# HDMI.net
KiCad netlist of a schematic drawn in Altium Designer
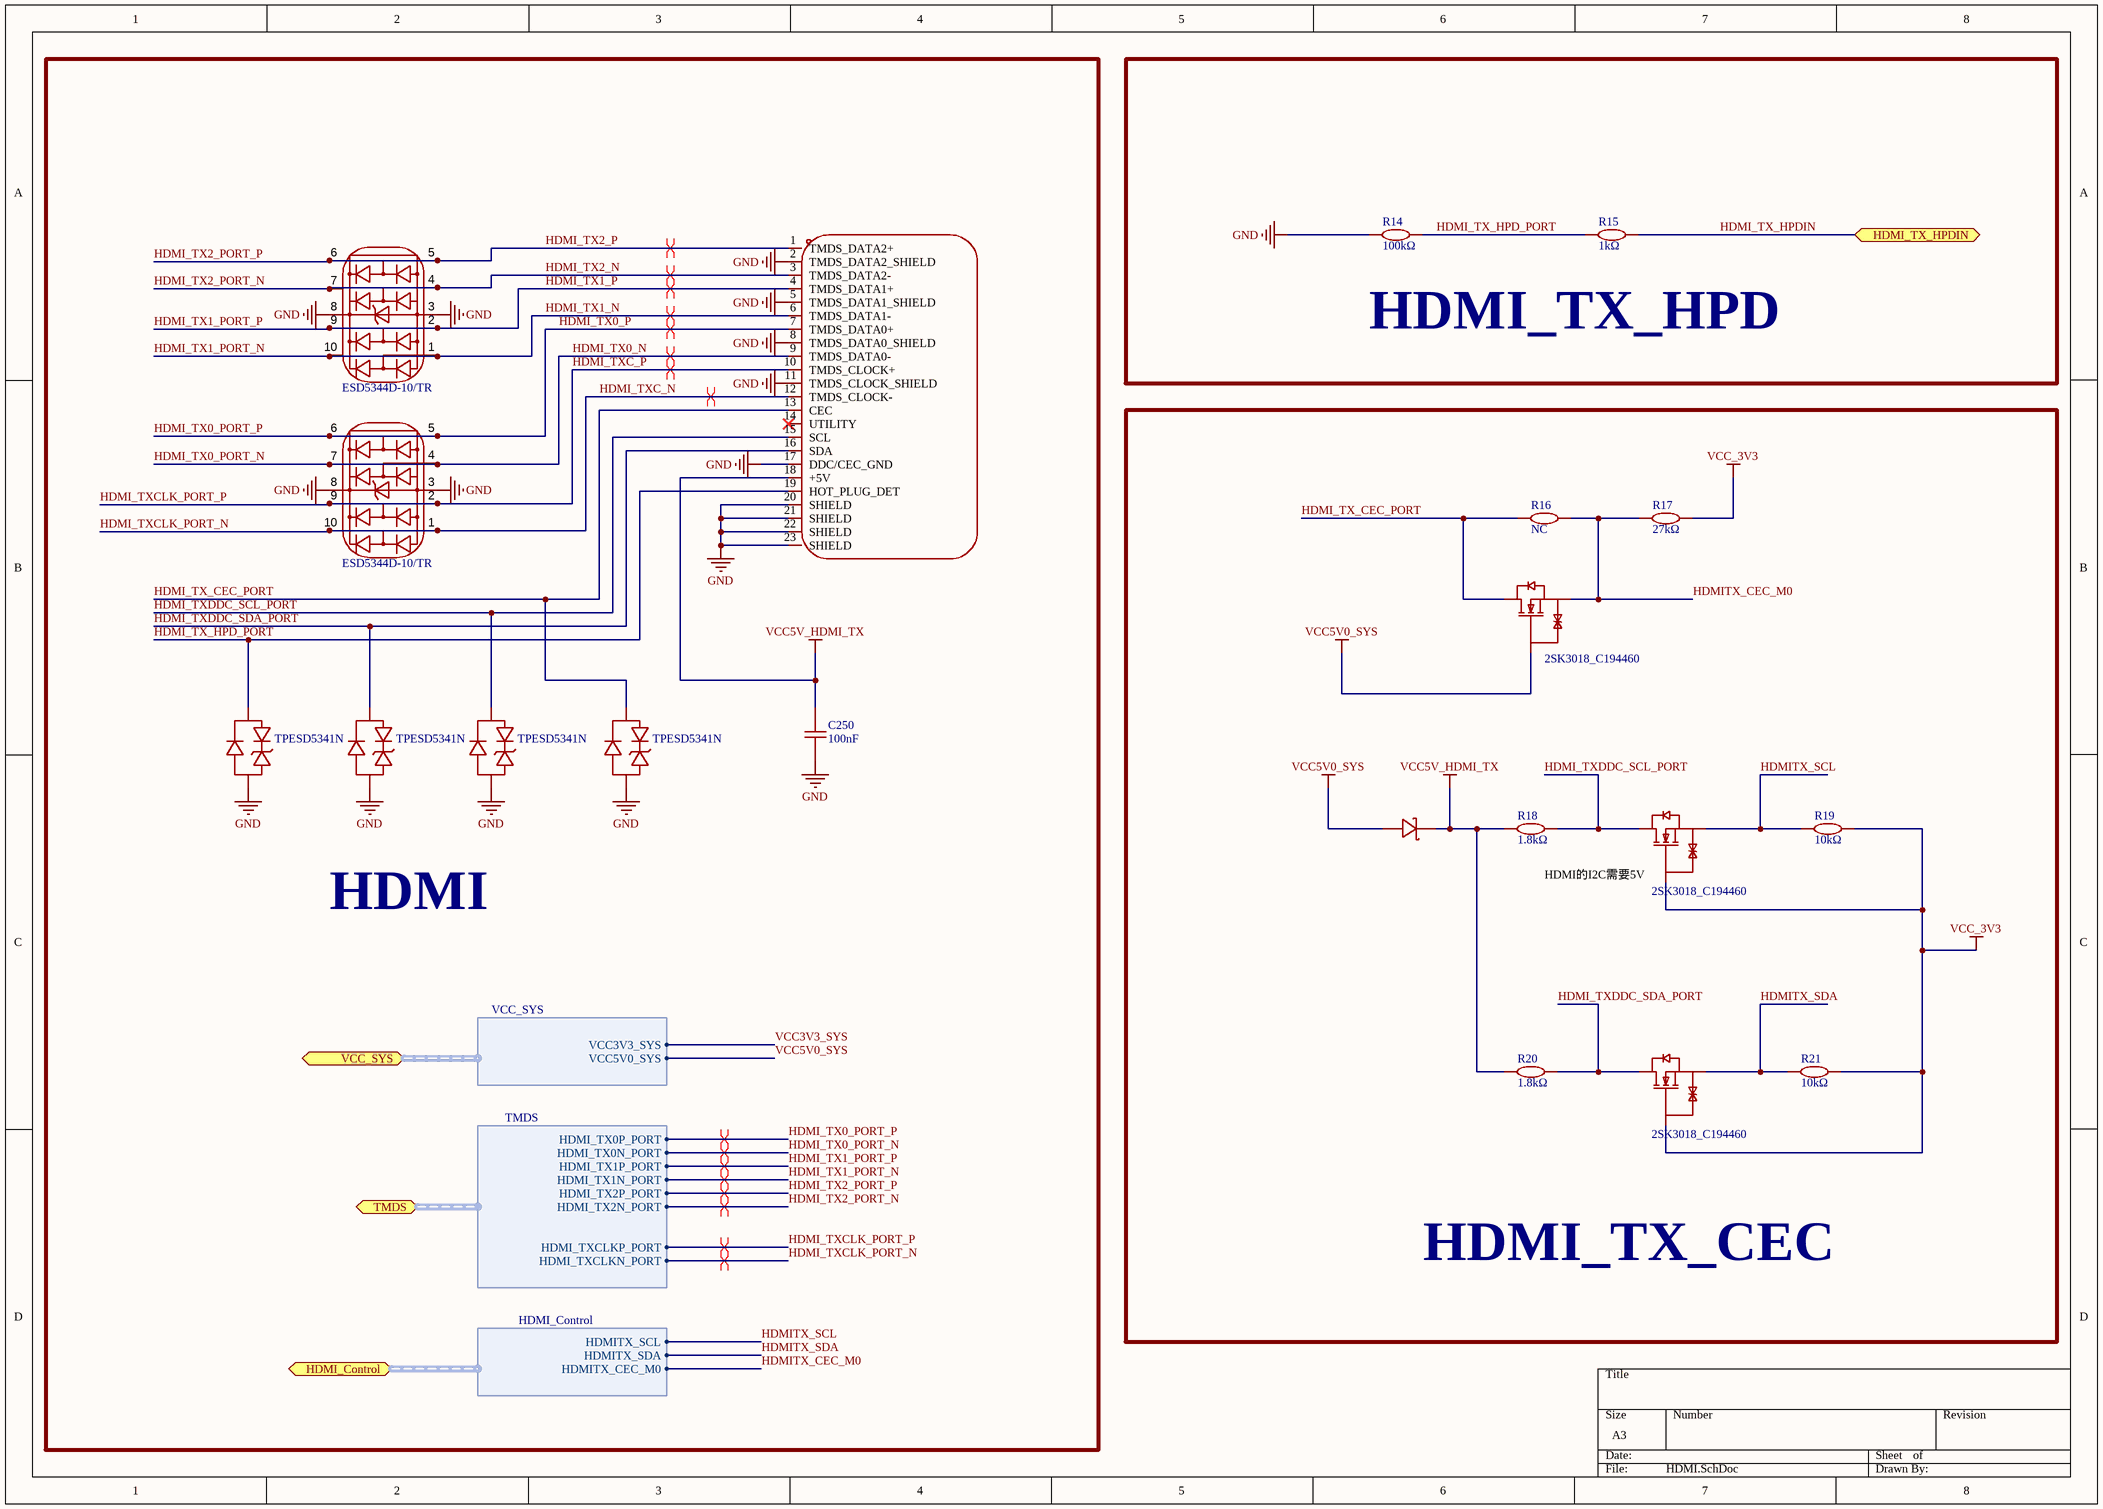
[diagram p0: HDMI.SchDoc]

(export (version "E")
  (design (tool "Eeschema 10.0.6"))
  (components
    (comp (ref "C250")
      (value "100nF")
      (footprint "C0402")
      (description "50V 100nF X7R ±10% 0402 Ceramic Capacitors ROHS")
      (libsource (lib "RLC") (part "100nF"))
    )
    (comp (ref "CN1")
      (value "KH-HDMI-19P-Cu")
      (footprint "HDMI-SMD_KH-HDMI-19P-CU")
      (description "HDMI-A SMD USB, DVI, HDMI Connector Assemblies ROHS")
      (fields (field (name "MANUFACTURER") "kinghelm(金航标)"))
      (libsource (lib "Connector") (part "KH-HDMI-19P-Cu"))
    )
    (comp (ref "D1")
      (value "ESD5344D-10/TR")
      (footprint "DFN2510-10_L2.5-W1.0-P0.50-BL")
      (libsource (lib "IC") (part "ESD5344D-10/TR"))
    )
    (comp (ref "D2")
      (value "ESD5344D-10/TR")
      (footprint "DFN2510-10_L2.5-W1.0-P0.50-BL")
      (libsource (lib "IC") (part "ESD5344D-10/TR"))
    )
    (comp (ref "D3")
      (value "TPESD5341N")
      (footprint "X1-DFN1006-2_L1.0-W0.6-RD")
      (description "VRWM:5V, IPP:3.3A, CJ:0.35pF")
      (libsource (lib "IC") (part "TPESD5341N"))
    )
    (comp (ref "D4")
      (value "TPESD5341N")
      (footprint "X1-DFN1006-2_L1.0-W0.6-RD")
      (description "VRWM:5V, IPP:3.3A, CJ:0.35pF")
      (libsource (lib "IC") (part "TPESD5341N"))
    )
    (comp (ref "D5")
      (value "TPESD5341N")
      (footprint "X1-DFN1006-2_L1.0-W0.6-RD")
      (description "VRWM:5V, IPP:3.3A, CJ:0.35pF")
      (libsource (lib "IC") (part "TPESD5341N"))
    )
    (comp (ref "D6")
      (value "TPESD5341N")
      (footprint "X1-DFN1006-2_L1.0-W0.6-RD")
      (description "VRWM:5V, IPP:3.3A, CJ:0.35pF")
      (libsource (lib "IC") (part "TPESD5341N"))
    )
    (comp (ref "D7")
      (value "1N5819WS")
      (footprint "SOD-323_L1.8-W1.3-LS2.5-RD")
      (description "25A 40V 600mV@1A 1A SOD-323 Single Diodes ROHS")
      (fields (field (name "MANUFACTURER") "Hottech(合科泰)"))
      (libsource (lib "LED") (part "1N5819WS_C191023"))
    )
    (comp (ref "Q1")
      (value "2SK3018_C194460")
      (footprint "SOT-23-3_L2.9-W1.3-P1.90-LS2.3-BR")
      (description "N沟道,30V,100mA")
      (libsource (lib "Transistor") (part "2SK3018_C194460"))
    )
    (comp (ref "Q2")
      (value "2SK3018_C194460")
      (footprint "SOT-23-3_L2.9-W1.3-P1.90-LS2.3-BR")
      (description "N沟道,30V,100mA")
      (libsource (lib "Transistor") (part "2SK3018_C194460"))
    )
    (comp (ref "Q3")
      (value "2SK3018_C194460")
      (footprint "SOT-23-3_L2.9-W1.3-P1.90-LS2.3-BR")
      (description "N沟道,30V,100mA")
      (libsource (lib "Transistor") (part "2SK3018_C194460"))
    )
    (comp (ref "R14")
      (value "100kΩ")
      (footprint "R0402")
      (description "100kΩ 62.5mW 50V ±100ppm/℃ Thick Film Resistor ±1% 0402 Chip Resistor - Surface Mount ROHS")
      (libsource (lib "RLC") (part "100kΩ"))
    )
    (comp (ref "R15")
      (value "1kΩ")
      (footprint "R0402")
      (description "1kΩ 62.5mW 50V ±100ppm/℃ Thick Film Resistor ±1% 0402 Chip Resistor - Surface Mount ROHS")
      (libsource (lib "RLC") (part "1kΩ"))
    )
    (comp (ref "R16")
      (value "NC")
      (footprint "R0402")
      (description "0Ω 62.5mW 50V Thick Film Resistor ±1% 0402 Chip Resistor - Surface Mount ROHS")
      (libsource (lib "RLC") (part "0Ω"))
    )
    (comp (ref "R17")
      (value "27kΩ")
      (footprint "R0402")
      (description "小尺寸、重量轻。降低组装成本,与贴片机匹配。适用于波峰焊和回流焊")
      (libsource (lib "RLC") (part "27kΩ"))
    )
    (comp (ref "R18")
      (value "1.8kΩ")
      (footprint "R0402")
      (description "62.5mW 1.8kΩ 50V ±100ppm/℃ Thick Film Resistor ±1% 0402 Chip Resistor - Surface Mount ROHS")
      (libsource (lib "RLC") (part "1.8kΩ"))
    )
    (comp (ref "R19")
      (value "10kΩ")
      (footprint "R0402")
      (description "62.5mW 10kΩ 50V ±100ppm/℃ Thick Film Resistor ±1% 0402 Chip Resistor - Surface Mount ROHS")
      (libsource (lib "RLC") (part "10kΩ"))
    )
    (comp (ref "R20")
      (value "1.8kΩ")
      (footprint "R0402")
      (description "62.5mW 1.8kΩ 50V ±100ppm/℃ Thick Film Resistor ±1% 0402 Chip Resistor - Surface Mount ROHS")
      (libsource (lib "RLC") (part "1.8kΩ"))
    )
    (comp (ref "R21")
      (value "10kΩ")
      (footprint "R0402")
      (description "62.5mW 10kΩ 50V ±100ppm/℃ Thick Film Resistor ±1% 0402 Chip Resistor - Surface Mount ROHS")
      (libsource (lib "RLC") (part "10kΩ"))
    )
  )
  (nets
    (net (code "4") (name "/HDMITX_CEC_M0") (class "Default")
      (node (ref "Q1") (pin "2") (pinfunction "S_2") (pintype "passive"))
      (node (ref "R16") (pin "2") (pinfunction "2_2") (pintype "passive"))
      (node (ref "R17") (pin "1") (pinfunction "1_1") (pintype "passive"))
    )
    (net (code "5") (name "/HDMITX_SCL") (class "Default")
      (node (ref "Q2") (pin "2") (pinfunction "S_2") (pintype "passive"))
      (node (ref "R19") (pin "1") (pinfunction "1_1") (pintype "passive"))
    )
    (net (code "6") (name "/HDMITX_SDA") (class "Default")
      (node (ref "Q3") (pin "2") (pinfunction "S_2") (pintype "passive"))
      (node (ref "R21") (pin "1") (pinfunction "1_1") (pintype "passive"))
    )
    (net (code "7") (name "/HDMI_TX0_N") (class "Default")
      (node (ref "CN1") (pin "9") (pinfunction "TMDS_DATA0-_9") (pintype "passive"))
      (node (ref "D2") (pin "4") (pinfunction "4_4") (pintype "passive"))
      (node (ref "D2") (pin "7") (pinfunction "7_7") (pintype "passive"))
    )
    (net (code "8") (name "/HDMI_TX0_P") (class "Default")
      (node (ref "CN1") (pin "7") (pinfunction "TMDS_DATA0+_7") (pintype "passive"))
      (node (ref "D2") (pin "5") (pinfunction "5_5") (pintype "passive"))
      (node (ref "D2") (pin "6") (pinfunction "6_6") (pintype "passive"))
    )
    (net (code "9") (name "/HDMI_TX1_N") (class "Default")
      (node (ref "CN1") (pin "6") (pinfunction "TMDS_DATA1-_6") (pintype "passive"))
      (node (ref "D1") (pin "1") (pinfunction "1_1") (pintype "passive"))
      (node (ref "D1") (pin "10") (pinfunction "10_10") (pintype "passive"))
    )
    (net (code "10") (name "/HDMI_TX1_P") (class "Default")
      (node (ref "CN1") (pin "4") (pinfunction "TMDS_DATA1+_4") (pintype "passive"))
      (node (ref "D1") (pin "2") (pinfunction "2_2") (pintype "passive"))
      (node (ref "D1") (pin "9") (pinfunction "9_9") (pintype "passive"))
    )
    (net (code "11") (name "/HDMI_TX2_N") (class "Default")
      (node (ref "CN1") (pin "3") (pinfunction "TMDS_DATA2-_3") (pintype "passive"))
      (node (ref "D1") (pin "4") (pinfunction "4_4") (pintype "passive"))
      (node (ref "D1") (pin "7") (pinfunction "7_7") (pintype "passive"))
    )
    (net (code "12") (name "/HDMI_TX2_P") (class "Default")
      (node (ref "CN1") (pin "1") (pinfunction "TMDS_DATA2+_1") (pintype "passive"))
      (node (ref "D1") (pin "5") (pinfunction "5_5") (pintype "passive"))
      (node (ref "D1") (pin "6") (pinfunction "6_6") (pintype "passive"))
    )
    (net (code "13") (name "/HDMI_TXCLK_PORT_N") (class "Default")
      (node (ref "CN1") (pin "12") (pinfunction "TMDS_CLOCK-_12") (pintype "passive"))
      (node (ref "D2") (pin "1") (pinfunction "1_1") (pintype "passive"))
      (node (ref "D2") (pin "10") (pinfunction "10_10") (pintype "passive"))
    )
    (net (code "14") (name "/HDMI_TXCLK_PORT_P") (class "Default")
      (node (ref "CN1") (pin "10") (pinfunction "TMDS_CLOCK+_10") (pintype "passive"))
      (node (ref "D2") (pin "2") (pinfunction "2_2") (pintype "passive"))
      (node (ref "D2") (pin "9") (pinfunction "9_9") (pintype "passive"))
    )
    (net (code "15") (name "/HDMI_TXDDC_SCL_PORT") (class "Default")
      (node (ref "CN1") (pin "15") (pinfunction "SCL_15") (pintype "passive"))
      (node (ref "D5") (pin "1") (pinfunction "1_1") (pintype "passive"))
      (node (ref "Q2") (pin "3") (pinfunction "D_3") (pintype "passive"))
      (node (ref "R18") (pin "2") (pinfunction "2_2") (pintype "passive"))
    )
    (net (code "16") (name "/HDMI_TXDDC_SDA_PORT") (class "Default")
      (node (ref "CN1") (pin "16") (pinfunction "SDA_16") (pintype "passive"))
      (node (ref "D4") (pin "1") (pinfunction "1_1") (pintype "passive"))
      (node (ref "Q3") (pin "3") (pinfunction "D_3") (pintype "passive"))
      (node (ref "R20") (pin "2") (pinfunction "2_2") (pintype "passive"))
    )
    (net (code "17") (name "/HDMI_TX_CEC_PORT") (class "Default")
      (node (ref "CN1") (pin "13") (pinfunction "CEC_13") (pintype "passive"))
      (node (ref "D6") (pin "1") (pinfunction "1_1") (pintype "passive"))
      (node (ref "Q1") (pin "3") (pinfunction "D_3") (pintype "passive"))
      (node (ref "R16") (pin "1") (pinfunction "1_1") (pintype "passive"))
    )
    (net (code "18") (name "/HDMI_TX_HPDIN") (class "Default")
      (node (ref "R15") (pin "2") (pinfunction "2_2") (pintype "passive"))
    )
    (net (code "19") (name "/HDMI_TX_HPD_PORT") (class "Default")
      (node (ref "CN1") (pin "19") (pinfunction "HOT_PLUG_DET_19") (pintype "passive"))
      (node (ref "D3") (pin "1") (pinfunction "1_1") (pintype "passive"))
      (node (ref "R14") (pin "2") (pinfunction "2_2") (pintype "passive"))
      (node (ref "R15") (pin "1") (pinfunction "1_1") (pintype "passive"))
    )
    (net (code "24") (name "GND") (class "Default")
      (node (ref "C250") (pin "1") (pinfunction "1_1") (pintype "passive"))
      (node (ref "CN1") (pin "11") (pinfunction "TMDS_CLOCK_SHIELD_11") (pintype "passive"))
      (node (ref "CN1") (pin "17") (pinfunction "DDC/CEC_GND_17") (pintype "passive"))
      (node (ref "CN1") (pin "2") (pinfunction "TMDS_DATA2_SHIELD_2") (pintype "passive"))
      (node (ref "CN1") (pin "20") (pinfunction "SHIELD_20") (pintype "passive"))
      (node (ref "CN1") (pin "21") (pinfunction "SHIELD_21") (pintype "passive"))
      (node (ref "CN1") (pin "22") (pinfunction "SHIELD_22") (pintype "passive"))
      (node (ref "CN1") (pin "23") (pinfunction "SHIELD_23") (pintype "passive"))
      (node (ref "CN1") (pin "5") (pinfunction "TMDS_DATA1_SHIELD_5") (pintype "passive"))
      (node (ref "CN1") (pin "8") (pinfunction "TMDS_DATA0_SHIELD_8") (pintype "passive"))
      (node (ref "D1") (pin "3") (pinfunction "3_3") (pintype "passive"))
      (node (ref "D1") (pin "8") (pinfunction "8_8") (pintype "passive"))
      (node (ref "D2") (pin "3") (pinfunction "3_3") (pintype "passive"))
      (node (ref "D2") (pin "8") (pinfunction "8_8") (pintype "passive"))
      (node (ref "D3") (pin "2") (pinfunction "2_2") (pintype "passive"))
      (node (ref "D4") (pin "2") (pinfunction "2_2") (pintype "passive"))
      (node (ref "D5") (pin "2") (pinfunction "2_2") (pintype "passive"))
      (node (ref "D6") (pin "2") (pinfunction "2_2") (pintype "passive"))
      (node (ref "R14") (pin "1") (pinfunction "1_1") (pintype "passive"))
    )
    (net (code "25") (name "VCC5V0_SYS") (class "Default")
      (node (ref "D7") (pin "2") (pinfunction "A_2") (pintype "passive"))
      (node (ref "Q1") (pin "1") (pinfunction "G_1") (pintype "passive"))
    )
    (net (code "26") (name "VCC5V_HDMI_TX") (class "Default")
      (node (ref "C250") (pin "2") (pinfunction "2_2") (pintype "passive"))
      (node (ref "CN1") (pin "18") (pinfunction "+5V_18") (pintype "passive"))
      (node (ref "D7") (pin "1") (pinfunction "K_1") (pintype "passive"))
      (node (ref "R18") (pin "1") (pinfunction "1_1") (pintype "passive"))
      (node (ref "R20") (pin "1") (pinfunction "1_1") (pintype "passive"))
    )
    (net (code "27") (name "VCC_3V3") (class "Default")
      (node (ref "Q2") (pin "1") (pinfunction "G_1") (pintype "passive"))
      (node (ref "Q3") (pin "1") (pinfunction "G_1") (pintype "passive"))
      (node (ref "R17") (pin "2") (pinfunction "2_2") (pintype "passive"))
      (node (ref "R19") (pin "2") (pinfunction "2_2") (pintype "passive"))
      (node (ref "R21") (pin "2") (pinfunction "2_2") (pintype "passive"))
    )
    (net (code "28") (name "unconnected-(CN1-UTILITY-Pad14)") (class "Default")
      (node (ref "CN1") (pin "14") (pinfunction "UTILITY_14") (pintype "passive+no_connect"))
    )
  )
)
